# spectrum.net
KiCad netlist of a schematic drawn in EAGLE
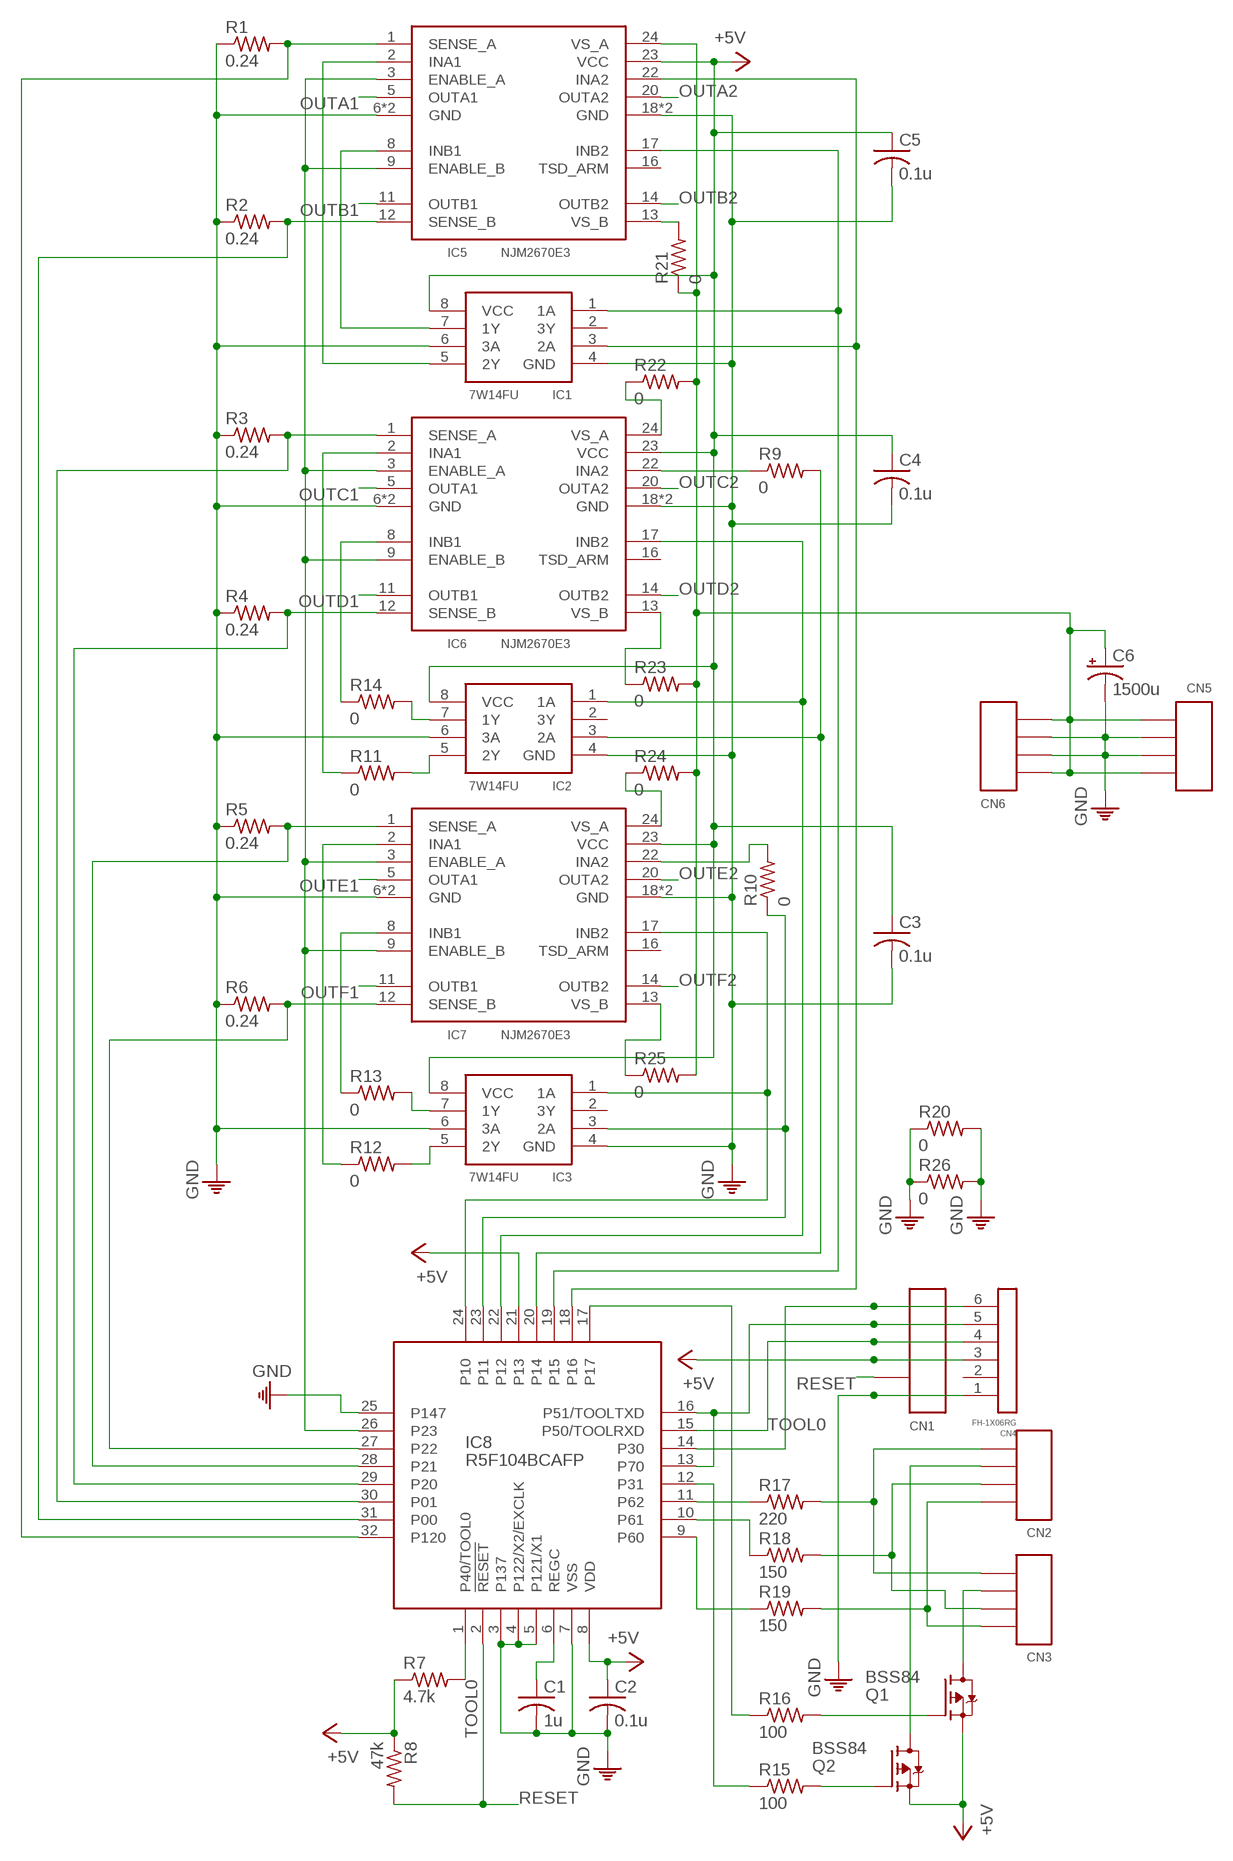
[diagram p0: schematic, sheet 1]

(export (version "E")
  (design (tool "Eeschema 10.0.6"))
  (components
    (comp (ref "C1")
      (value "1u")
      (footprint "eagle-import:C2012")
      (libsource (lib "eagle-import") (part "C2012"))
    )
    (comp (ref "C2")
      (value "0.1u")
      (footprint "eagle-import:C2012")
      (libsource (lib "eagle-import") (part "C2012"))
    )
    (comp (ref "C3")
      (value "0.1u")
      (footprint "eagle-import:C2012")
      (libsource (lib "eagle-import") (part "C2012"))
    )
    (comp (ref "C4")
      (value "0.1u")
      (footprint "eagle-import:C2012")
      (libsource (lib "eagle-import") (part "C2012"))
    )
    (comp (ref "C5")
      (value "0.1u")
      (footprint "eagle-import:C2012")
      (libsource (lib "eagle-import") (part "C2012"))
    )
    (comp (ref "C6")
      (value "1500u")
      (footprint "eagle-import:E3,5-8")
      (libsource (lib "eagle-import") (part "CCE3.5-8"))
    )
    (comp (ref "CN1")
      (value "PH-1X06RG")
      (footprint "eagle-import:PH-1X06RG")
      (libsource (lib "eagle-import") (part "PH-1X06RG"))
    )
    (comp (ref "CN2")
      (value "PH-1X04SG")
      (footprint "eagle-import:PH-1X04SG")
      (libsource (lib "eagle-import") (part "PH-1X04SG"))
    )
    (comp (ref "CN3")
      (value "PH-1X04SG")
      (footprint "eagle-import:PH-1X04SG")
      (libsource (lib "eagle-import") (part "PH-1X04SG"))
    )
    (comp (ref "CN4")
      (value "FH-1X06RG")
      (footprint "eagle-import:FH-1X06RG")
      (libsource (lib "eagle-import") (part "FH-1X06RG"))
    )
    (comp (ref "CN5")
      (value "PH-1X04SGRG")
      (footprint "eagle-import:PH-1X04RG")
      (libsource (lib "eagle-import") (part "PH-1X04SGRG"))
    )
    (comp (ref "CN6")
      (value "FH-1X04RG")
      (footprint "eagle-import:FH-1X04RG")
      (libsource (lib "eagle-import") (part "FH-1X04RG"))
    )
    (comp (ref "IC1")
      (value "7W14FU")
      (footprint "eagle-import:SSOP8-P-0.65")
      (libsource (lib "eagle-import") (part "714FUW"))
    )
    (comp (ref "IC2")
      (value "7W14FU")
      (footprint "eagle-import:SSOP8-P-0.65")
      (libsource (lib "eagle-import") (part "714FUW"))
    )
    (comp (ref "IC3")
      (value "7W14FU")
      (footprint "eagle-import:SSOP8-P-0.65")
      (libsource (lib "eagle-import") (part "714FUW"))
    )
    (comp (ref "IC5")
      (value "NJM2670E3")
      (footprint "eagle-import:EMP-24")
      (libsource (lib "eagle-import") (part "NJM2670E3"))
    )
    (comp (ref "IC6")
      (value "NJM2670E3")
      (footprint "eagle-import:EMP-24")
      (libsource (lib "eagle-import") (part "NJM2670E3"))
    )
    (comp (ref "IC7")
      (value "NJM2670E3")
      (footprint "eagle-import:EMP-24")
      (libsource (lib "eagle-import") (part "NJM2670E3"))
    )
    (comp (ref "IC8")
      (value "R5F104BCAFP")
      (footprint "eagle-import:P-LQFP32-7X7-0.80")
      (libsource (lib "eagle-import") (part "R5F104BFPCA"))
    )
    (comp (ref "Q1")
      (value "BSS84")
      (footprint "eagle-import:SOT-23F")
      (libsource (lib "eagle-import") (part "BSS84"))
    )
    (comp (ref "Q2")
      (value "BSS84")
      (footprint "eagle-import:SOT-23F")
      (libsource (lib "eagle-import") (part "BSS84"))
    )
    (comp (ref "R1")
      (value "0.24")
      (footprint "eagle-import:R3225")
      (libsource (lib "eagle-import") (part "R3225"))
    )
    (comp (ref "R2")
      (value "0.24")
      (footprint "eagle-import:R3225")
      (libsource (lib "eagle-import") (part "R3225"))
    )
    (comp (ref "R3")
      (value "0.24")
      (footprint "eagle-import:R3225")
      (libsource (lib "eagle-import") (part "R3225"))
    )
    (comp (ref "R4")
      (value "0.24")
      (footprint "eagle-import:R3225")
      (libsource (lib "eagle-import") (part "R3225"))
    )
    (comp (ref "R5")
      (value "0.24")
      (footprint "eagle-import:R3225")
      (libsource (lib "eagle-import") (part "R3225"))
    )
    (comp (ref "R6")
      (value "0.24")
      (footprint "eagle-import:R3225")
      (libsource (lib "eagle-import") (part "R3225"))
    )
    (comp (ref "R7")
      (value "4.7k")
      (footprint "eagle-import:R2012")
      (libsource (lib "eagle-import") (part "R2012"))
    )
    (comp (ref "R8")
      (value "47k")
      (footprint "eagle-import:R2012")
      (libsource (lib "eagle-import") (part "R2012"))
    )
    (comp (ref "R9")
      (value "0")
      (footprint "eagle-import:R2012")
      (libsource (lib "eagle-import") (part "R2012"))
    )
    (comp (ref "R10")
      (value "0")
      (footprint "eagle-import:R2012")
      (libsource (lib "eagle-import") (part "R2012"))
    )
    (comp (ref "R11")
      (value "0")
      (footprint "eagle-import:R2012")
      (libsource (lib "eagle-import") (part "R2012"))
    )
    (comp (ref "R12")
      (value "0")
      (footprint "eagle-import:R2012")
      (libsource (lib "eagle-import") (part "R2012"))
    )
    (comp (ref "R13")
      (value "0")
      (footprint "eagle-import:R2012")
      (libsource (lib "eagle-import") (part "R2012"))
    )
    (comp (ref "R14")
      (value "0")
      (footprint "eagle-import:R2012")
      (libsource (lib "eagle-import") (part "R2012"))
    )
    (comp (ref "R15")
      (value "100")
      (footprint "eagle-import:R2012")
      (libsource (lib "eagle-import") (part "R2012"))
    )
    (comp (ref "R16")
      (value "100")
      (footprint "eagle-import:R2012")
      (libsource (lib "eagle-import") (part "R2012"))
    )
    (comp (ref "R17")
      (value "220")
      (footprint "eagle-import:R2012")
      (libsource (lib "eagle-import") (part "R2012"))
    )
    (comp (ref "R18")
      (value "150")
      (footprint "eagle-import:R2012")
      (libsource (lib "eagle-import") (part "R2012"))
    )
    (comp (ref "R19")
      (value "150")
      (footprint "eagle-import:R2012")
      (libsource (lib "eagle-import") (part "R2012"))
    )
    (comp (ref "R20")
      (value "0")
      (footprint "eagle-import:0204_5")
      (libsource (lib "eagle-import") (part "R0204/5"))
    )
    (comp (ref "R21")
      (value "0")
      (footprint "eagle-import:0204_7")
      (libsource (lib "eagle-import") (part "R0204/7"))
    )
    (comp (ref "R22")
      (value "0")
      (footprint "eagle-import:0204_7")
      (libsource (lib "eagle-import") (part "R0204/7"))
    )
    (comp (ref "R23")
      (value "0")
      (footprint "eagle-import:0204_7")
      (libsource (lib "eagle-import") (part "R0204/7"))
    )
    (comp (ref "R24")
      (value "0")
      (footprint "eagle-import:0204_7")
      (libsource (lib "eagle-import") (part "R0204/7"))
    )
    (comp (ref "R25")
      (value "0")
      (footprint "eagle-import:0204_7")
      (libsource (lib "eagle-import") (part "R0204/7"))
    )
    (comp (ref "R26")
      (value "0")
      (footprint "eagle-import:0204_5")
      (libsource (lib "eagle-import") (part "R0204/5"))
    )
  )
  (nets
    (net (code "1") (name "+5V") (class "Default")
      (node (ref "C2") (pin "1") (pinfunction "1_1") (pintype "passive"))
      (node (ref "C3") (pin "1") (pinfunction "1_1") (pintype "passive"))
      (node (ref "C4") (pin "1") (pinfunction "1_1") (pintype "passive"))
      (node (ref "C5") (pin "1") (pinfunction "1_1") (pintype "passive"))
      (node (ref "CN1") (pin "P$4") (pinfunction "P$4_P$4") (pintype "bidirectional"))
      (node (ref "CN4") (pin "3") (pinfunction "P$3_3") (pintype "passive"))
      (node (ref "IC1") (pin "8") (pinfunction "VCC_8") (pintype "power_in"))
      (node (ref "IC2") (pin "8") (pinfunction "VCC_8") (pintype "power_in"))
      (node (ref "IC3") (pin "8") (pinfunction "VCC_8") (pintype "power_in"))
      (node (ref "IC5") (pin "23") (pinfunction "VCC_23") (pintype "power_in"))
      (node (ref "IC6") (pin "23") (pinfunction "VCC_23") (pintype "power_in"))
      (node (ref "IC7") (pin "23") (pinfunction "VCC_23") (pintype "power_in"))
      (node (ref "IC8") (pin "21") (pinfunction "P13_21") (pintype "bidirectional"))
      (node (ref "IC8") (pin "8") (pinfunction "VDD_8") (pintype "bidirectional"))
      (node (ref "Q1") (pin "P$2") (pinfunction "S_P$2") (pintype "passive"))
      (node (ref "Q2") (pin "P$2") (pinfunction "S_P$2") (pintype "passive"))
      (node (ref "R7") (pin "1") (pinfunction "1_1") (pintype "passive"))
      (node (ref "R8") (pin "1") (pinfunction "1_1") (pintype "passive"))
    )
    (net (code "2") (name "/OUTA1") (class "Default")
      (node (ref "IC5") (pin "5") (pinfunction "OUTA1_5") (pintype "output"))
    )
    (net (code "3") (name "/OUTA2") (class "Default")
      (node (ref "IC5") (pin "20") (pinfunction "OUTA2_20") (pintype "output"))
    )
    (net (code "4") (name "/OUTB1") (class "Default")
      (node (ref "IC5") (pin "11") (pinfunction "OUTB1_11") (pintype "output"))
    )
    (net (code "5") (name "/OUTB2") (class "Default")
      (node (ref "IC5") (pin "14") (pinfunction "OUTB2_14") (pintype "output"))
    )
    (net (code "6") (name "/OUTC1") (class "Default")
      (node (ref "IC6") (pin "5") (pinfunction "OUTA1_5") (pintype "output"))
    )
    (net (code "7") (name "/OUTC2") (class "Default")
      (node (ref "IC6") (pin "20") (pinfunction "OUTA2_20") (pintype "output"))
    )
    (net (code "8") (name "/OUTD1") (class "Default")
      (node (ref "IC6") (pin "11") (pinfunction "OUTB1_11") (pintype "output"))
    )
    (net (code "9") (name "/OUTD2") (class "Default")
      (node (ref "IC6") (pin "14") (pinfunction "OUTB2_14") (pintype "output"))
    )
    (net (code "10") (name "/OUTE1") (class "Default")
      (node (ref "IC7") (pin "5") (pinfunction "OUTA1_5") (pintype "output"))
    )
    (net (code "11") (name "/OUTE2") (class "Default")
      (node (ref "IC7") (pin "20") (pinfunction "OUTA2_20") (pintype "output"))
    )
    (net (code "12") (name "/OUTF1") (class "Default")
      (node (ref "IC7") (pin "11") (pinfunction "OUTB1_11") (pintype "output"))
    )
    (net (code "13") (name "/OUTF2") (class "Default")
      (node (ref "IC7") (pin "14") (pinfunction "OUTB2_14") (pintype "output"))
    )
    (net (code "14") (name "/RESET") (class "Default")
      (node (ref "CN1") (pin "P$5") (pinfunction "P$5_P$5") (pintype "bidirectional"))
      (node (ref "IC8") (pin "2") (pinfunction "~{RESET}_2") (pintype "bidirectional"))
      (node (ref "R8") (pin "2") (pinfunction "2_2") (pintype "passive"))
    )
    (net (code "15") (name "/TOOL0") (class "Default")
      (node (ref "CN1") (pin "P$3") (pinfunction "P$3_P$3") (pintype "bidirectional"))
      (node (ref "CN4") (pin "4") (pinfunction "P$4_4") (pintype "passive"))
      (node (ref "IC8") (pin "1") (pinfunction "P40/TOOL0_1") (pintype "bidirectional"))
      (node (ref "IC8") (pin "15") (pinfunction "P50/TOOLRXD_15") (pintype "bidirectional"))
      (node (ref "R7") (pin "2") (pinfunction "2_2") (pintype "passive"))
    )
    (net (code "16") (name "GND") (class "Default")
      (node (ref "C1") (pin "2") (pinfunction "2_2") (pintype "passive"))
      (node (ref "C2") (pin "2") (pinfunction "2_2") (pintype "passive"))
      (node (ref "C3") (pin "2") (pinfunction "2_2") (pintype "passive"))
      (node (ref "C4") (pin "2") (pinfunction "2_2") (pintype "passive"))
      (node (ref "C5") (pin "2") (pinfunction "2_2") (pintype "passive"))
      (node (ref "C6") (pin "-") (pinfunction "-_-") (pintype "passive"))
      (node (ref "CN1") (pin "P$6") (pinfunction "P$6_P$6") (pintype "bidirectional"))
      (node (ref "CN4") (pin "1") (pinfunction "P$1_1") (pintype "passive"))
      (node (ref "CN5") (pin "2") (pinfunction "P$2_2") (pintype "passive"))
      (node (ref "CN5") (pin "3") (pinfunction "P$3_3") (pintype "passive"))
      (node (ref "CN6") (pin "2") (pinfunction "P$2_2") (pintype "passive"))
      (node (ref "CN6") (pin "3") (pinfunction "P$3_3") (pintype "passive"))
      (node (ref "IC1") (pin "4") (pinfunction "GND_4") (pintype "power_in"))
      (node (ref "IC1") (pin "6") (pinfunction "3A_6") (pintype "input"))
      (node (ref "IC2") (pin "4") (pinfunction "GND_4") (pintype "power_in"))
      (node (ref "IC2") (pin "6") (pinfunction "3A_6") (pintype "input"))
      (node (ref "IC3") (pin "4") (pinfunction "GND_4") (pintype "power_in"))
      (node (ref "IC3") (pin "6") (pinfunction "3A_6") (pintype "input"))
      (node (ref "IC5") (pin "18") (pinfunction "GND_18") (pintype "power_in"))
      (node (ref "IC5") (pin "19") (pinfunction "GND_19") (pintype "power_in"))
      (node (ref "IC5") (pin "6") (pinfunction "GND_6") (pintype "power_in"))
      (node (ref "IC5") (pin "7") (pinfunction "GND_7") (pintype "power_in"))
      (node (ref "IC6") (pin "18") (pinfunction "GND_18") (pintype "power_in"))
      (node (ref "IC6") (pin "19") (pinfunction "GND_19") (pintype "power_in"))
      (node (ref "IC6") (pin "6") (pinfunction "GND_6") (pintype "power_in"))
      (node (ref "IC6") (pin "7") (pinfunction "GND_7") (pintype "power_in"))
      (node (ref "IC7") (pin "18") (pinfunction "GND_18") (pintype "power_in"))
      (node (ref "IC7") (pin "19") (pinfunction "GND_19") (pintype "power_in"))
      (node (ref "IC7") (pin "6") (pinfunction "GND_6") (pintype "power_in"))
      (node (ref "IC7") (pin "7") (pinfunction "GND_7") (pintype "power_in"))
      (node (ref "IC8") (pin "25") (pinfunction "P147_25") (pintype "bidirectional"))
      (node (ref "IC8") (pin "3") (pinfunction "P137_3") (pintype "bidirectional"))
      (node (ref "IC8") (pin "4") (pinfunction "P122/X2/EXCLK_4") (pintype "bidirectional"))
      (node (ref "IC8") (pin "5") (pinfunction "P121/X1_5") (pintype "bidirectional"))
      (node (ref "IC8") (pin "7") (pinfunction "VSS_7") (pintype "bidirectional"))
      (node (ref "R1") (pin "1") (pinfunction "1_1") (pintype "passive"))
      (node (ref "R2") (pin "1") (pinfunction "1_1") (pintype "passive"))
      (node (ref "R20") (pin "1") (pinfunction "1_1") (pintype "passive"))
      (node (ref "R20") (pin "2") (pinfunction "2_2") (pintype "passive"))
      (node (ref "R26") (pin "1") (pinfunction "1_1") (pintype "passive"))
      (node (ref "R26") (pin "2") (pinfunction "2_2") (pintype "passive"))
      (node (ref "R3") (pin "1") (pinfunction "1_1") (pintype "passive"))
      (node (ref "R4") (pin "1") (pinfunction "1_1") (pintype "passive"))
      (node (ref "R5") (pin "1") (pinfunction "1_1") (pintype "passive"))
      (node (ref "R6") (pin "1") (pinfunction "1_1") (pintype "passive"))
    )
    (net (code "17") (name "Net-(CN2-PadP$1)") (class "Default")
      (node (ref "CN2") (pin "P$1") (pinfunction "P$1_P$1") (pintype "passive"))
      (node (ref "CN3") (pin "P$1") (pinfunction "P$1_P$1") (pintype "passive"))
      (node (ref "R17") (pin "2") (pinfunction "2_2") (pintype "passive"))
    )
    (net (code "18") (name "Net-(CN2-PadP$3)") (class "Default")
      (node (ref "CN2") (pin "P$3") (pinfunction "P$3_P$3") (pintype "passive"))
      (node (ref "CN3") (pin "P$3") (pinfunction "P$3_P$3") (pintype "passive"))
      (node (ref "R18") (pin "2") (pinfunction "2_2") (pintype "passive"))
    )
    (net (code "19") (name "Net-(CN2-PadP$4)") (class "Default")
      (node (ref "CN2") (pin "P$4") (pinfunction "P$4_P$4") (pintype "passive"))
      (node (ref "CN3") (pin "P$4") (pinfunction "P$4_P$4") (pintype "passive"))
      (node (ref "R19") (pin "2") (pinfunction "2_2") (pintype "passive"))
    )
    (net (code "20") (name "Net-(CN4-P$5)") (class "Default")
      (node (ref "CN1") (pin "P$2") (pinfunction "P$2_P$2") (pintype "bidirectional"))
      (node (ref "CN4") (pin "5") (pinfunction "P$5_5") (pintype "passive"))
      (node (ref "IC8") (pin "13") (pinfunction "P70_13") (pintype "bidirectional"))
      (node (ref "IC8") (pin "16") (pinfunction "P51/TOOLTXD_16") (pintype "bidirectional"))
    )
    (net (code "21") (name "Net-(CN4-P$6)") (class "Default")
      (node (ref "CN1") (pin "P$1") (pinfunction "P$1_P$1") (pintype "bidirectional"))
      (node (ref "CN4") (pin "6") (pinfunction "P$6_6") (pintype "passive"))
      (node (ref "IC8") (pin "14") (pinfunction "P30_14") (pintype "bidirectional"))
    )
    (net (code "22") (name "Net-(CN5-P$1)") (class "Default")
      (node (ref "C6") (pin "+") (pinfunction "+_+") (pintype "passive"))
      (node (ref "CN5") (pin "1") (pinfunction "P$1_1") (pintype "passive"))
      (node (ref "CN5") (pin "4") (pinfunction "P$4_4") (pintype "passive"))
      (node (ref "CN6") (pin "1") (pinfunction "P$1_1") (pintype "passive"))
      (node (ref "CN6") (pin "4") (pinfunction "P$4_4") (pintype "passive"))
      (node (ref "IC5") (pin "24") (pinfunction "VS_A_24") (pintype "power_in"))
      (node (ref "R21") (pin "1") (pinfunction "1_1") (pintype "passive"))
      (node (ref "R22") (pin "2") (pinfunction "2_2") (pintype "passive"))
      (node (ref "R23") (pin "2") (pinfunction "2_2") (pintype "passive"))
      (node (ref "R24") (pin "2") (pinfunction "2_2") (pintype "passive"))
      (node (ref "R25") (pin "2") (pinfunction "2_2") (pintype "passive"))
    )
    (net (code "23") (name "Net-(IC1-1A)") (class "Default")
      (node (ref "IC1") (pin "1") (pinfunction "1A_1") (pintype "input"))
      (node (ref "IC5") (pin "17") (pinfunction "INB2_17") (pintype "input"))
      (node (ref "IC8") (pin "19") (pinfunction "P15_19") (pintype "bidirectional"))
    )
    (net (code "24") (name "Net-(IC1-1Y)") (class "Default")
      (node (ref "IC1") (pin "7") (pinfunction "1Y_7") (pintype "output"))
      (node (ref "IC5") (pin "8") (pinfunction "INB1_8") (pintype "input"))
    )
    (net (code "25") (name "Net-(IC1-2A)") (class "Default")
      (node (ref "IC1") (pin "3") (pinfunction "2A_3") (pintype "input"))
      (node (ref "IC5") (pin "22") (pinfunction "INA2_22") (pintype "input"))
      (node (ref "IC8") (pin "18") (pinfunction "P16_18") (pintype "bidirectional"))
    )
    (net (code "26") (name "Net-(IC1-2Y)") (class "Default")
      (node (ref "IC1") (pin "5") (pinfunction "2Y_5") (pintype "output"))
      (node (ref "IC5") (pin "2") (pinfunction "INA1_2") (pintype "input"))
    )
    (net (code "27") (name "Net-(IC2-1A)") (class "Default")
      (node (ref "IC2") (pin "1") (pinfunction "1A_1") (pintype "input"))
      (node (ref "IC6") (pin "17") (pinfunction "INB2_17") (pintype "input"))
      (node (ref "IC8") (pin "22") (pinfunction "P12_22") (pintype "bidirectional"))
    )
    (net (code "28") (name "Net-(IC2-1Y)") (class "Default")
      (node (ref "IC2") (pin "7") (pinfunction "1Y_7") (pintype "output"))
      (node (ref "R14") (pin "2") (pinfunction "2_2") (pintype "passive"))
    )
    (net (code "29") (name "Net-(IC2-2A)") (class "Default")
      (node (ref "IC2") (pin "3") (pinfunction "2A_3") (pintype "input"))
      (node (ref "IC8") (pin "20") (pinfunction "P14_20") (pintype "bidirectional"))
      (node (ref "R9") (pin "2") (pinfunction "2_2") (pintype "passive"))
    )
    (net (code "30") (name "Net-(IC2-2Y)") (class "Default")
      (node (ref "IC2") (pin "5") (pinfunction "2Y_5") (pintype "output"))
      (node (ref "R11") (pin "2") (pinfunction "2_2") (pintype "passive"))
    )
    (net (code "31") (name "Net-(IC3-1A)") (class "Default")
      (node (ref "IC3") (pin "1") (pinfunction "1A_1") (pintype "input"))
      (node (ref "IC7") (pin "17") (pinfunction "INB2_17") (pintype "input"))
      (node (ref "IC8") (pin "24") (pinfunction "P10_24") (pintype "bidirectional"))
    )
    (net (code "32") (name "Net-(IC3-1Y)") (class "Default")
      (node (ref "IC3") (pin "7") (pinfunction "1Y_7") (pintype "output"))
      (node (ref "R13") (pin "2") (pinfunction "2_2") (pintype "passive"))
    )
    (net (code "33") (name "Net-(IC3-2A)") (class "Default")
      (node (ref "IC3") (pin "3") (pinfunction "2A_3") (pintype "input"))
      (node (ref "IC8") (pin "23") (pinfunction "P11_23") (pintype "bidirectional"))
      (node (ref "R10") (pin "1") (pinfunction "1_1") (pintype "passive"))
    )
    (net (code "34") (name "Net-(IC3-2Y)") (class "Default")
      (node (ref "IC3") (pin "5") (pinfunction "2Y_5") (pintype "output"))
      (node (ref "R12") (pin "2") (pinfunction "2_2") (pintype "passive"))
    )
    (net (code "35") (name "Net-(IC5-ENABLE_A)") (class "Default")
      (node (ref "IC5") (pin "3") (pinfunction "ENABLE_A_3") (pintype "power_in"))
      (node (ref "IC5") (pin "9") (pinfunction "ENABLE_B_9") (pintype "power_in"))
      (node (ref "IC6") (pin "3") (pinfunction "ENABLE_A_3") (pintype "power_in"))
      (node (ref "IC6") (pin "9") (pinfunction "ENABLE_B_9") (pintype "power_in"))
      (node (ref "IC7") (pin "3") (pinfunction "ENABLE_A_3") (pintype "power_in"))
      (node (ref "IC7") (pin "9") (pinfunction "ENABLE_B_9") (pintype "power_in"))
      (node (ref "IC8") (pin "26") (pinfunction "P23_26") (pintype "bidirectional"))
    )
    (net (code "36") (name "Net-(IC5-SENSE_A)") (class "Default")
      (node (ref "IC5") (pin "1") (pinfunction "SENSE_A_1") (pintype "passive"))
      (node (ref "IC8") (pin "32") (pinfunction "P120_32") (pintype "bidirectional"))
      (node (ref "R1") (pin "2") (pinfunction "2_2") (pintype "passive"))
    )
    (net (code "37") (name "Net-(IC5-SENSE_B)") (class "Default")
      (node (ref "IC5") (pin "12") (pinfunction "SENSE_B_12") (pintype "passive"))
      (node (ref "IC8") (pin "31") (pinfunction "P00_31") (pintype "bidirectional"))
      (node (ref "R2") (pin "2") (pinfunction "2_2") (pintype "passive"))
    )
    (net (code "38") (name "Net-(IC5-VS_B)") (class "Default")
      (node (ref "IC5") (pin "13") (pinfunction "VS_B_13") (pintype "power_in"))
      (node (ref "R21") (pin "2") (pinfunction "2_2") (pintype "passive"))
    )
    (net (code "39") (name "Net-(IC6-INA1)") (class "Default")
      (node (ref "IC6") (pin "2") (pinfunction "INA1_2") (pintype "input"))
      (node (ref "R11") (pin "1") (pinfunction "1_1") (pintype "passive"))
    )
    (net (code "40") (name "Net-(IC6-INA2)") (class "Default")
      (node (ref "IC6") (pin "22") (pinfunction "INA2_22") (pintype "input"))
      (node (ref "R9") (pin "1") (pinfunction "1_1") (pintype "passive"))
    )
    (net (code "41") (name "Net-(IC6-INB1)") (class "Default")
      (node (ref "IC6") (pin "8") (pinfunction "INB1_8") (pintype "input"))
      (node (ref "R14") (pin "1") (pinfunction "1_1") (pintype "passive"))
    )
    (net (code "42") (name "Net-(IC6-SENSE_A)") (class "Default")
      (node (ref "IC6") (pin "1") (pinfunction "SENSE_A_1") (pintype "passive"))
      (node (ref "IC8") (pin "30") (pinfunction "P01_30") (pintype "bidirectional"))
      (node (ref "R3") (pin "2") (pinfunction "2_2") (pintype "passive"))
    )
    (net (code "43") (name "Net-(IC6-SENSE_B)") (class "Default")
      (node (ref "IC6") (pin "12") (pinfunction "SENSE_B_12") (pintype "passive"))
      (node (ref "IC8") (pin "29") (pinfunction "P20_29") (pintype "bidirectional"))
      (node (ref "R4") (pin "2") (pinfunction "2_2") (pintype "passive"))
    )
    (net (code "44") (name "Net-(IC6-VS_A)") (class "Default")
      (node (ref "IC6") (pin "24") (pinfunction "VS_A_24") (pintype "power_in"))
      (node (ref "R22") (pin "1") (pinfunction "1_1") (pintype "passive"))
    )
    (net (code "45") (name "Net-(IC6-VS_B)") (class "Default")
      (node (ref "IC6") (pin "13") (pinfunction "VS_B_13") (pintype "power_in"))
      (node (ref "R23") (pin "1") (pinfunction "1_1") (pintype "passive"))
    )
    (net (code "46") (name "Net-(IC7-INA1)") (class "Default")
      (node (ref "IC7") (pin "2") (pinfunction "INA1_2") (pintype "input"))
      (node (ref "R12") (pin "1") (pinfunction "1_1") (pintype "passive"))
    )
    (net (code "47") (name "Net-(IC7-INA2)") (class "Default")
      (node (ref "IC7") (pin "22") (pinfunction "INA2_22") (pintype "input"))
      (node (ref "R10") (pin "2") (pinfunction "2_2") (pintype "passive"))
    )
    (net (code "48") (name "Net-(IC7-INB1)") (class "Default")
      (node (ref "IC7") (pin "8") (pinfunction "INB1_8") (pintype "input"))
      (node (ref "R13") (pin "1") (pinfunction "1_1") (pintype "passive"))
    )
    (net (code "49") (name "Net-(IC7-SENSE_A)") (class "Default")
      (node (ref "IC7") (pin "1") (pinfunction "SENSE_A_1") (pintype "passive"))
      (node (ref "IC8") (pin "28") (pinfunction "P21_28") (pintype "bidirectional"))
      (node (ref "R5") (pin "2") (pinfunction "2_2") (pintype "passive"))
    )
    (net (code "50") (name "Net-(IC7-SENSE_B)") (class "Default")
      (node (ref "IC7") (pin "12") (pinfunction "SENSE_B_12") (pintype "passive"))
      (node (ref "IC8") (pin "27") (pinfunction "P22_27") (pintype "bidirectional"))
      (node (ref "R6") (pin "2") (pinfunction "2_2") (pintype "passive"))
    )
    (net (code "51") (name "Net-(IC7-VS_A)") (class "Default")
      (node (ref "IC7") (pin "24") (pinfunction "VS_A_24") (pintype "power_in"))
      (node (ref "R24") (pin "1") (pinfunction "1_1") (pintype "passive"))
    )
    (net (code "52") (name "Net-(IC7-VS_B)") (class "Default")
      (node (ref "IC7") (pin "13") (pinfunction "VS_B_13") (pintype "power_in"))
      (node (ref "R25") (pin "1") (pinfunction "1_1") (pintype "passive"))
    )
    (net (code "53") (name "Net-(IC8-P17)") (class "Default")
      (node (ref "IC8") (pin "17") (pinfunction "P17_17") (pintype "bidirectional"))
      (node (ref "R16") (pin "1") (pinfunction "1_1") (pintype "passive"))
    )
    (net (code "54") (name "Net-(IC8-P31)") (class "Default")
      (node (ref "IC8") (pin "12") (pinfunction "P31_12") (pintype "bidirectional"))
      (node (ref "R15") (pin "1") (pinfunction "1_1") (pintype "passive"))
    )
    (net (code "55") (name "Net-(IC8-P60)") (class "Default")
      (node (ref "IC8") (pin "9") (pinfunction "P60_9") (pintype "bidirectional"))
      (node (ref "R19") (pin "1") (pinfunction "1_1") (pintype "passive"))
    )
    (net (code "56") (name "Net-(IC8-P61)") (class "Default")
      (node (ref "IC8") (pin "10") (pinfunction "P61_10") (pintype "bidirectional"))
      (node (ref "R18") (pin "1") (pinfunction "1_1") (pintype "passive"))
    )
    (net (code "57") (name "Net-(IC8-P62)") (class "Default")
      (node (ref "IC8") (pin "11") (pinfunction "P62_11") (pintype "bidirectional"))
      (node (ref "R17") (pin "1") (pinfunction "1_1") (pintype "passive"))
    )
    (net (code "58") (name "Net-(IC8-REGC)") (class "Default")
      (node (ref "C1") (pin "1") (pinfunction "1_1") (pintype "passive"))
      (node (ref "IC8") (pin "6") (pinfunction "REGC_6") (pintype "bidirectional"))
    )
    (net (code "59") (name "Net-(Q1-D)") (class "Default")
      (node (ref "CN3") (pin "P$2") (pinfunction "P$2_P$2") (pintype "passive"))
      (node (ref "Q1") (pin "P$3") (pinfunction "D_P$3") (pintype "passive"))
    )
    (net (code "60") (name "Net-(Q1-G)") (class "Default")
      (node (ref "Q1") (pin "P$1") (pinfunction "G_P$1") (pintype "passive"))
      (node (ref "R16") (pin "2") (pinfunction "2_2") (pintype "passive"))
    )
    (net (code "61") (name "Net-(Q2-D)") (class "Default")
      (node (ref "CN2") (pin "P$2") (pinfunction "P$2_P$2") (pintype "passive"))
      (node (ref "Q2") (pin "P$3") (pinfunction "D_P$3") (pintype "passive"))
    )
    (net (code "62") (name "Net-(Q2-G)") (class "Default")
      (node (ref "Q2") (pin "P$1") (pinfunction "G_P$1") (pintype "passive"))
      (node (ref "R15") (pin "2") (pinfunction "2_2") (pintype "passive"))
    )
    (net (code "63") (name "unconnected-(CN4-P$2-Pad2)") (class "Default")
      (node (ref "CN4") (pin "2") (pinfunction "P$2_2") (pintype "passive"))
    )
    (net (code "64") (name "unconnected-(IC1-3Y-Pad2)") (class "Default")
      (node (ref "IC1") (pin "2") (pinfunction "3Y_2") (pintype "output"))
    )
    (net (code "65") (name "unconnected-(IC2-3Y-Pad2)") (class "Default")
      (node (ref "IC2") (pin "2") (pinfunction "3Y_2") (pintype "output"))
    )
    (net (code "66") (name "unconnected-(IC3-3Y-Pad2)") (class "Default")
      (node (ref "IC3") (pin "2") (pinfunction "3Y_2") (pintype "output"))
    )
    (net (code "67") (name "unconnected-(IC5-TSD_ARM-Pad16)") (class "Default")
      (node (ref "IC5") (pin "16") (pinfunction "TSD_ARM_16") (pintype "open_collector"))
    )
    (net (code "68") (name "unconnected-(IC6-TSD_ARM-Pad16)") (class "Default")
      (node (ref "IC6") (pin "16") (pinfunction "TSD_ARM_16") (pintype "open_collector"))
    )
    (net (code "69") (name "unconnected-(IC7-TSD_ARM-Pad16)") (class "Default")
      (node (ref "IC7") (pin "16") (pinfunction "TSD_ARM_16") (pintype "open_collector"))
    )
  )
)
